# MCU.net
KiCad netlist of a schematic drawn in Altium Designer
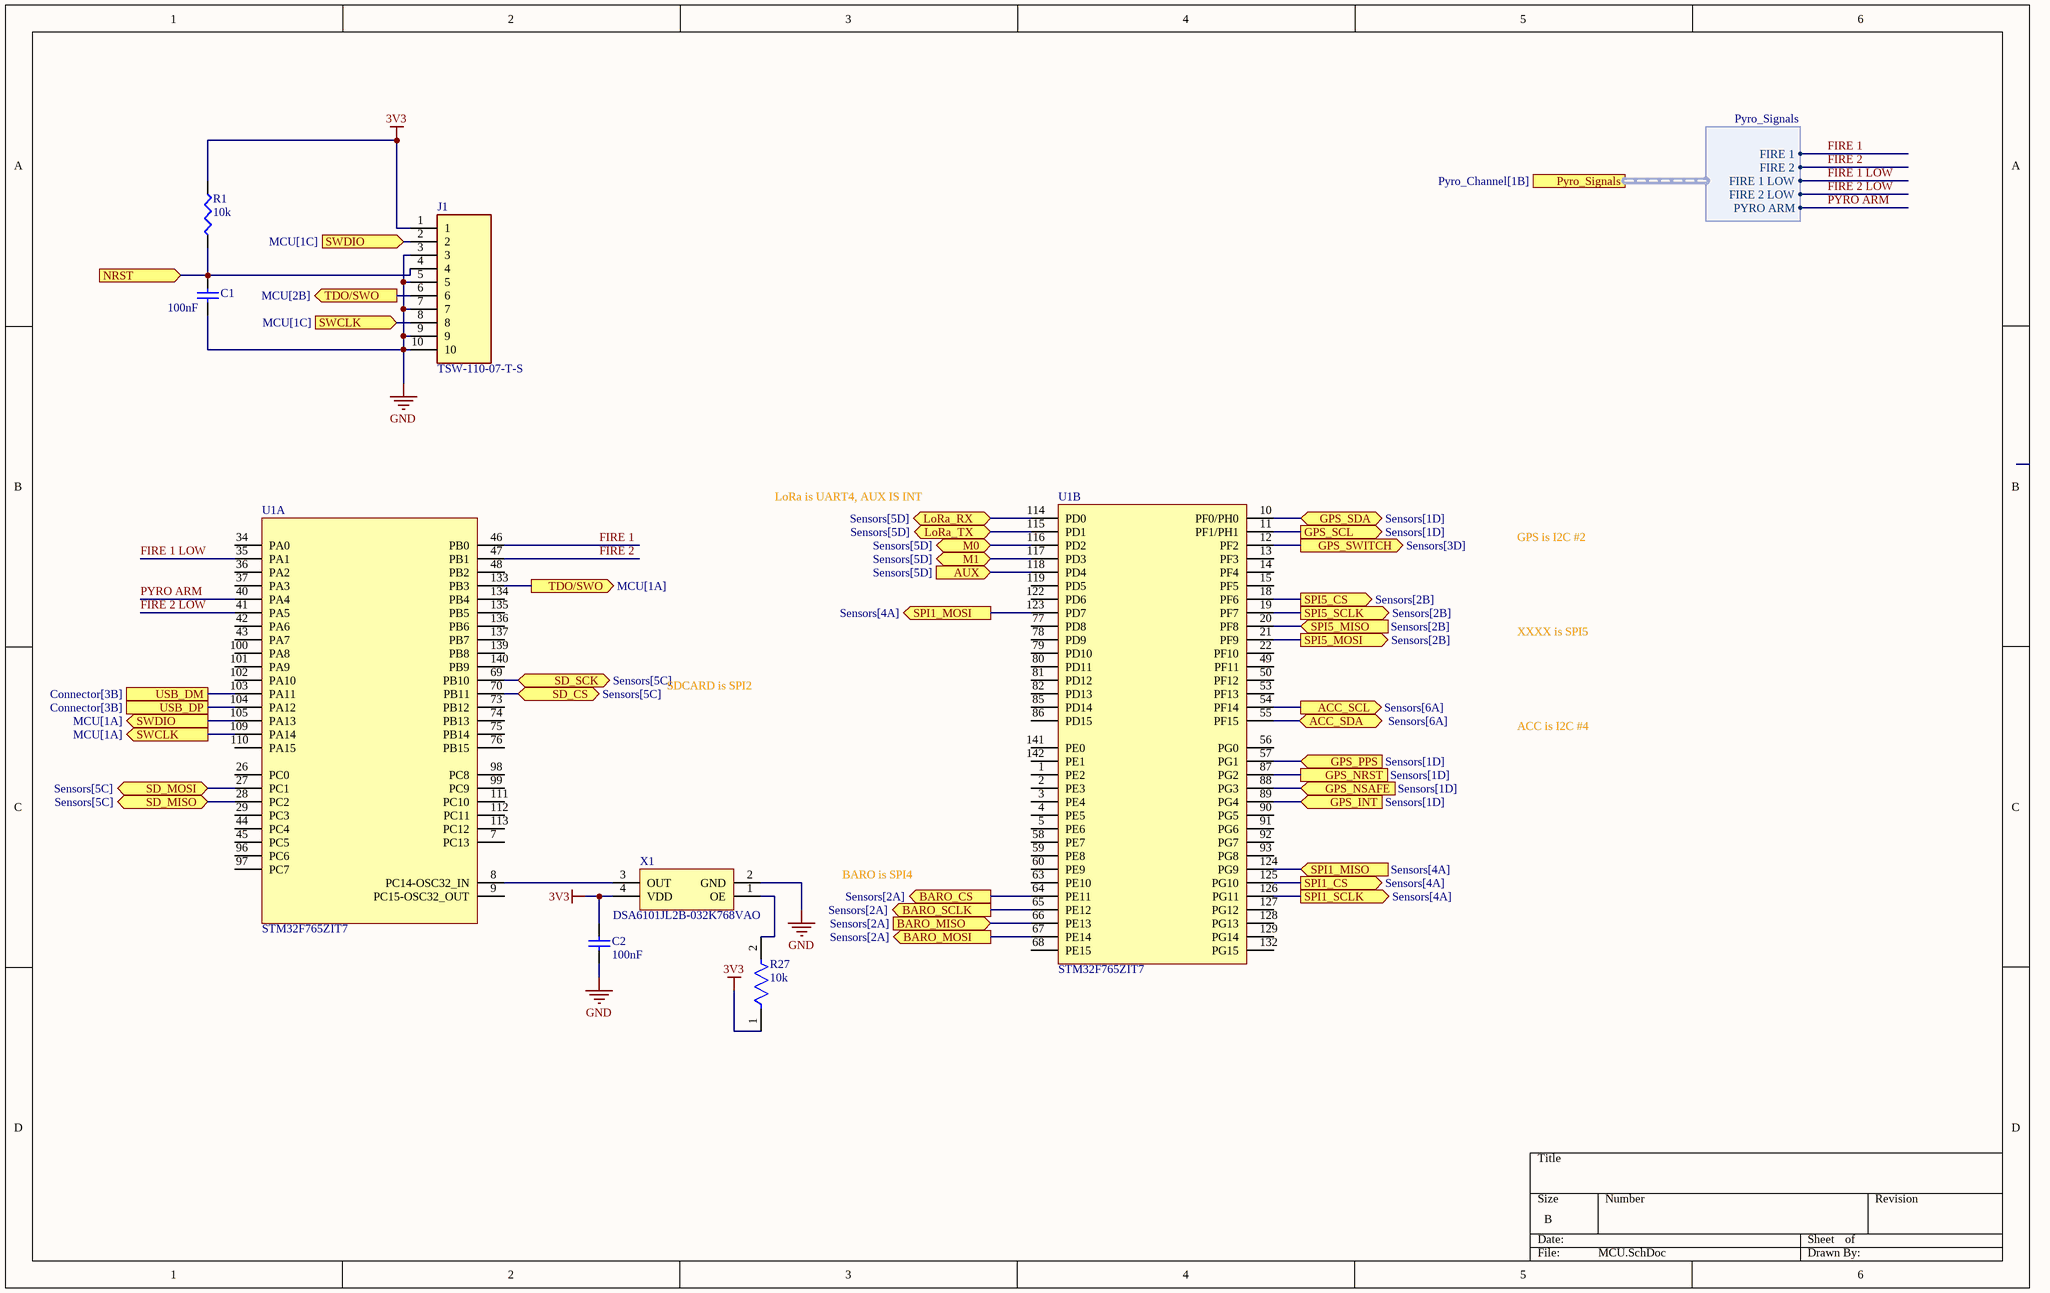
[diagram p0: MCU.SchDoc]

(export (version "E")
  (design (tool "Eeschema 10.0.6"))
  (components
    (comp (ref "C1")
      (value "100nF")
      (footprint "0402_C")
      (fields
        (field (name "MANUFACTURER") "Samsung Electro-Mechanics")
        (field (name "MANUFACTURER PART NUMBER") "CL05B104KO5NNNC")
        (field (name "TOLERANCE") "10%")
      )
      (libsource (lib "Flight_Computer1") (part "C_100nF_0402"))
    )
    (comp (ref "C2")
      (value "100nF")
      (footprint "0402_C")
      (fields
        (field (name "MANUFACTURER") "Samsung Electro-Mechanics")
        (field (name "MANUFACTURER PART NUMBER") "CL05B104KO5NNNC")
        (field (name "TOLERANCE") "10%")
      )
      (libsource (lib "Flight_Computer1") (part "C_100nF_0402"))
    )
    (comp (ref "J1")
      (value "TSW-110-07-T-S")
      (footprint "TSW-110-XX-YY-S")
      (description "CONN HEADER VERT 10POS 2.54MM")
      (fields (field (name "MOUSER PART NUMBER") "200-TSW11007TS") (field (name "MANUFACTURER") "Samtec"))
      (libsource (lib "Flight_Computer1") (part "TSW-110-07-T-S"))
    )
    (comp (ref "R1")
      (value "10k")
      (footprint "0402_R")
      (description "RES SMD 10K OHM 0.1% 1/16W 0402")
      (fields (field (name "LCSC PART #") "C191915") (field (name "MANUFACTURER") "Yageo Group"))
      (libsource (lib "Flight_Computer1") (part "R_10k_0402"))
    )
    (comp (ref "R27")
      (value "10k")
      (footprint "FP-AC0805-0_6-MFG")
      (description "RES SMD 0 OHM JUMPER 1/8W 0805")
      (fields (field (name "TOLERANCE") "5%"))
      (libsource (lib "Altium Content Vault") (part "1029c3af85768c4190bb7ad29bc67b5"))
    )
    (comp (ref "U1")
      (value "STM32F765ZIT7")
      (footprint "QFP50P2200X2200X160-144N")
      (description "Integrated Circuit")
      (fields (field (name "MOUSER PART NUMBER") "511-STM32F765ZIT7"))
      (libsource (lib "Flight_Computer1") (part "STM32F765ZIT7"))
    )
    (comp (ref "X1")
      (value "DSA6101JL2B-032K768VAO")
      (footprint "VLGA4_AUA_MCH")
      (description "Description")
      (fields (field (name "COPYRIGHT") "Copyright (C) 2025 Ultra Librarian. All rights reserved."))
      (libsource (lib "Americas - Purdue University - Purdue Space Program Hybrids") (part "DSA6101JL2B-032K768VAO"))
    )
  )
  (nets
    (net (code "2") (name "/ACC_SCL") (class "Default")
      (node (ref "U1") (pin "54") (pinfunction "PF14_54") (pintype "passive"))
    )
    (net (code "3") (name "/ACC_SDA") (class "Default")
      (node (ref "U1") (pin "55") (pinfunction "PF15_55") (pintype "passive"))
    )
    (net (code "4") (name "/AUX") (class "Default")
      (node (ref "U1") (pin "118") (pinfunction "PD4_118") (pintype "passive"))
    )
    (net (code "5") (name "/BARO_CS") (class "Default")
      (node (ref "U1") (pin "64") (pinfunction "PE11_64") (pintype "passive"))
    )
    (net (code "6") (name "/BARO_MISO") (class "Default")
      (node (ref "U1") (pin "66") (pinfunction "PE13_66") (pintype "passive"))
    )
    (net (code "7") (name "/BARO_MOSI") (class "Default")
      (node (ref "U1") (pin "67") (pinfunction "PE14_67") (pintype "passive"))
    )
    (net (code "8") (name "/BARO_SCLK") (class "Default")
      (node (ref "U1") (pin "65") (pinfunction "PE12_65") (pintype "passive"))
    )
    (net (code "9") (name "/FIRE 1") (class "Default")
      (node (ref "U1") (pin "46") (pinfunction "PB0_46") (pintype "passive"))
    )
    (net (code "10") (name "/FIRE 1 LOW") (class "Default")
      (node (ref "U1") (pin "35") (pinfunction "PA1_35") (pintype "passive"))
    )
    (net (code "11") (name "/FIRE 2") (class "Default")
      (node (ref "U1") (pin "47") (pinfunction "PB1_47") (pintype "passive"))
    )
    (net (code "12") (name "/FIRE 2 LOW") (class "Default")
      (node (ref "U1") (pin "41") (pinfunction "PA5_41") (pintype "passive"))
    )
    (net (code "13") (name "/GPS_INT") (class "Default")
      (node (ref "U1") (pin "89") (pinfunction "PG4_89") (pintype "passive"))
    )
    (net (code "14") (name "/GPS_NRST") (class "Default")
      (node (ref "U1") (pin "87") (pinfunction "PG2_87") (pintype "passive"))
    )
    (net (code "15") (name "/GPS_NSAFE") (class "Default")
      (node (ref "U1") (pin "88") (pinfunction "PG3_88") (pintype "passive"))
    )
    (net (code "16") (name "/GPS_PPS") (class "Default")
      (node (ref "U1") (pin "57") (pinfunction "PG1_57") (pintype "passive"))
    )
    (net (code "17") (name "/GPS_SCL") (class "Default")
      (node (ref "U1") (pin "11") (pinfunction "PF1/PH1_11") (pintype "passive"))
    )
    (net (code "18") (name "/GPS_SDA") (class "Default")
      (node (ref "U1") (pin "10") (pinfunction "PF0/PH0_10") (pintype "passive"))
    )
    (net (code "19") (name "/GPS_SWITCH") (class "Default")
      (node (ref "U1") (pin "12") (pinfunction "PF2_12") (pintype "passive"))
    )
    (net (code "20") (name "/LoRa_RX") (class "Default")
      (node (ref "U1") (pin "114") (pinfunction "PD0_114") (pintype "passive"))
    )
    (net (code "21") (name "/LoRa_TX") (class "Default")
      (node (ref "U1") (pin "115") (pinfunction "PD1_115") (pintype "passive"))
    )
    (net (code "22") (name "/M0") (class "Default")
      (node (ref "U1") (pin "116") (pinfunction "PD2_116") (pintype "passive"))
    )
    (net (code "23") (name "/M1") (class "Default")
      (node (ref "U1") (pin "117") (pinfunction "PD3_117") (pintype "passive"))
    )
    (net (code "24") (name "/NRST") (class "Default")
      (node (ref "C1") (pin "2") (pinfunction "2_2") (pintype "passive"))
      (node (ref "J1") (pin "4") (pinfunction "4_4") (pintype "passive"))
      (node (ref "R1") (pin "1") (pinfunction "1_1") (pintype "passive"))
    )
    (net (code "25") (name "/PYRO ARM") (class "Default")
      (node (ref "U1") (pin "40") (pinfunction "PA4_40") (pintype "passive"))
    )
    (net (code "26") (name "/SD_CS") (class "Default")
      (node (ref "U1") (pin "70") (pinfunction "PB11_70") (pintype "passive"))
    )
    (net (code "27") (name "/SD_MISO") (class "Default")
      (node (ref "U1") (pin "28") (pinfunction "PC2_28") (pintype "passive"))
    )
    (net (code "28") (name "/SD_MOSI") (class "Default")
      (node (ref "U1") (pin "27") (pinfunction "PC1_27") (pintype "passive"))
    )
    (net (code "29") (name "/SD_SCK") (class "Default")
      (node (ref "U1") (pin "69") (pinfunction "PB10_69") (pintype "passive"))
    )
    (net (code "30") (name "/SPI1_CS") (class "Default")
      (node (ref "U1") (pin "125") (pinfunction "PG10_125") (pintype "passive"))
    )
    (net (code "31") (name "/SPI1_MISO") (class "Default")
      (node (ref "U1") (pin "124") (pinfunction "PG9_124") (pintype "passive"))
    )
    (net (code "32") (name "/SPI1_MOSI") (class "Default")
      (node (ref "U1") (pin "123") (pinfunction "PD7_123") (pintype "passive"))
    )
    (net (code "33") (name "/SPI1_SCLK") (class "Default")
      (node (ref "U1") (pin "126") (pinfunction "PG11_126") (pintype "passive"))
    )
    (net (code "34") (name "/SPI5_CS") (class "Default")
      (node (ref "U1") (pin "18") (pinfunction "PF6_18") (pintype "passive"))
    )
    (net (code "35") (name "/SPI5_MISO") (class "Default")
      (node (ref "U1") (pin "20") (pinfunction "PF8_20") (pintype "passive"))
    )
    (net (code "36") (name "/SPI5_MOSI") (class "Default")
      (node (ref "U1") (pin "21") (pinfunction "PF9_21") (pintype "passive"))
    )
    (net (code "37") (name "/SPI5_SCLK") (class "Default")
      (node (ref "U1") (pin "19") (pinfunction "PF7_19") (pintype "passive"))
    )
    (net (code "38") (name "/SWCLK") (class "Default")
      (node (ref "J1") (pin "8") (pinfunction "8_8") (pintype "passive"))
      (node (ref "U1") (pin "109") (pinfunction "PA14_109") (pintype "passive"))
    )
    (net (code "39") (name "/SWDIO") (class "Default")
      (node (ref "J1") (pin "2") (pinfunction "2_2") (pintype "passive"))
      (node (ref "U1") (pin "105") (pinfunction "PA13_105") (pintype "passive"))
    )
    (net (code "40") (name "/TDO{slash}SWO") (class "Default")
      (node (ref "J1") (pin "6") (pinfunction "6_6") (pintype "passive"))
      (node (ref "U1") (pin "133") (pinfunction "PB3_133") (pintype "passive"))
    )
    (net (code "41") (name "/USB_DM") (class "Default")
      (node (ref "U1") (pin "103") (pinfunction "PA11_103") (pintype "passive"))
    )
    (net (code "42") (name "/USB_DP") (class "Default")
      (node (ref "U1") (pin "104") (pinfunction "PA12_104") (pintype "passive"))
    )
    (net (code "44") (name "3V3") (class "Default")
      (node (ref "C2") (pin "1") (pinfunction "1_1") (pintype "passive"))
      (node (ref "J1") (pin "1") (pinfunction "1_1") (pintype "passive"))
      (node (ref "R1") (pin "2") (pinfunction "2_2") (pintype "passive"))
      (node (ref "R27") (pin "1") (pinfunction "1_1") (pintype "passive"))
      (node (ref "X1") (pin "4") (pinfunction "VDD_4") (pintype "passive"))
    )
    (net (code "45") (name "GND") (class "Default")
      (node (ref "C1") (pin "1") (pinfunction "1_1") (pintype "passive"))
      (node (ref "C2") (pin "2") (pinfunction "2_2") (pintype "passive"))
      (node (ref "J1") (pin "10") (pinfunction "10_10") (pintype "passive"))
      (node (ref "J1") (pin "3") (pinfunction "3_3") (pintype "passive"))
      (node (ref "J1") (pin "5") (pinfunction "5_5") (pintype "passive"))
      (node (ref "J1") (pin "7") (pinfunction "7_7") (pintype "passive"))
      (node (ref "J1") (pin "9") (pinfunction "9_9") (pintype "passive"))
      (node (ref "X1") (pin "2") (pinfunction "GND_2") (pintype "passive"))
    )
    (net (code "46") (name "Net-(U1A-PC14-OSC32_IN)") (class "Default")
      (node (ref "U1") (pin "8") (pinfunction "PC14-OSC32_IN_8") (pintype "passive"))
      (node (ref "X1") (pin "3") (pinfunction "OUT_3") (pintype "passive"))
    )
    (net (code "47") (name "Net-(X1-OE)") (class "Default")
      (node (ref "R27") (pin "2") (pinfunction "2_2") (pintype "passive"))
      (node (ref "X1") (pin "1") (pinfunction "OE_1") (pintype "passive"))
    )
    (net (code "48") (name "unconnected-(U1A-PA0-Pad34)") (class "Default")
      (node (ref "U1") (pin "34") (pinfunction "PA0_34") (pintype "passive"))
    )
    (net (code "49") (name "unconnected-(U1A-PA2-Pad36)") (class "Default")
      (node (ref "U1") (pin "36") (pinfunction "PA2_36") (pintype "passive"))
    )
    (net (code "50") (name "unconnected-(U1A-PA3-Pad37)") (class "Default")
      (node (ref "U1") (pin "37") (pinfunction "PA3_37") (pintype "passive"))
    )
    (net (code "51") (name "unconnected-(U1A-PA6-Pad42)") (class "Default")
      (node (ref "U1") (pin "42") (pinfunction "PA6_42") (pintype "passive"))
    )
    (net (code "52") (name "unconnected-(U1A-PA7-Pad43)") (class "Default")
      (node (ref "U1") (pin "43") (pinfunction "PA7_43") (pintype "passive"))
    )
    (net (code "53") (name "unconnected-(U1A-PA8-Pad100)") (class "Default")
      (node (ref "U1") (pin "100") (pinfunction "PA8_100") (pintype "passive"))
    )
    (net (code "54") (name "unconnected-(U1A-PA9-Pad101)") (class "Default")
      (node (ref "U1") (pin "101") (pinfunction "PA9_101") (pintype "passive"))
    )
    (net (code "55") (name "unconnected-(U1A-PA10-Pad102)") (class "Default")
      (node (ref "U1") (pin "102") (pinfunction "PA10_102") (pintype "passive"))
    )
    (net (code "56") (name "unconnected-(U1A-PA15-Pad110)") (class "Default")
      (node (ref "U1") (pin "110") (pinfunction "PA15_110") (pintype "passive"))
    )
    (net (code "57") (name "unconnected-(U1A-PB2-Pad48)") (class "Default")
      (node (ref "U1") (pin "48") (pinfunction "PB2_48") (pintype "passive"))
    )
    (net (code "58") (name "unconnected-(U1A-PB4-Pad134)") (class "Default")
      (node (ref "U1") (pin "134") (pinfunction "PB4_134") (pintype "passive"))
    )
    (net (code "59") (name "unconnected-(U1A-PB5-Pad135)") (class "Default")
      (node (ref "U1") (pin "135") (pinfunction "PB5_135") (pintype "passive"))
    )
    (net (code "60") (name "unconnected-(U1A-PB6-Pad136)") (class "Default")
      (node (ref "U1") (pin "136") (pinfunction "PB6_136") (pintype "passive"))
    )
    (net (code "61") (name "unconnected-(U1A-PB7-Pad137)") (class "Default")
      (node (ref "U1") (pin "137") (pinfunction "PB7_137") (pintype "passive"))
    )
    (net (code "62") (name "unconnected-(U1A-PB8-Pad139)") (class "Default")
      (node (ref "U1") (pin "139") (pinfunction "PB8_139") (pintype "passive"))
    )
    (net (code "63") (name "unconnected-(U1A-PB9-Pad140)") (class "Default")
      (node (ref "U1") (pin "140") (pinfunction "PB9_140") (pintype "passive"))
    )
    (net (code "64") (name "unconnected-(U1A-PB12-Pad73)") (class "Default")
      (node (ref "U1") (pin "73") (pinfunction "PB12_73") (pintype "passive"))
    )
    (net (code "65") (name "unconnected-(U1A-PB13-Pad74)") (class "Default")
      (node (ref "U1") (pin "74") (pinfunction "PB13_74") (pintype "passive"))
    )
    (net (code "66") (name "unconnected-(U1A-PB14-Pad75)") (class "Default")
      (node (ref "U1") (pin "75") (pinfunction "PB14_75") (pintype "passive"))
    )
    (net (code "67") (name "unconnected-(U1A-PB15-Pad76)") (class "Default")
      (node (ref "U1") (pin "76") (pinfunction "PB15_76") (pintype "passive"))
    )
    (net (code "68") (name "unconnected-(U1A-PC0-Pad26)") (class "Default")
      (node (ref "U1") (pin "26") (pinfunction "PC0_26") (pintype "passive"))
    )
    (net (code "69") (name "unconnected-(U1A-PC3-Pad29)") (class "Default")
      (node (ref "U1") (pin "29") (pinfunction "PC3_29") (pintype "passive"))
    )
    (net (code "70") (name "unconnected-(U1A-PC4-Pad44)") (class "Default")
      (node (ref "U1") (pin "44") (pinfunction "PC4_44") (pintype "passive"))
    )
    (net (code "71") (name "unconnected-(U1A-PC5-Pad45)") (class "Default")
      (node (ref "U1") (pin "45") (pinfunction "PC5_45") (pintype "passive"))
    )
    (net (code "72") (name "unconnected-(U1A-PC6-Pad96)") (class "Default")
      (node (ref "U1") (pin "96") (pinfunction "PC6_96") (pintype "passive"))
    )
    (net (code "73") (name "unconnected-(U1A-PC7-Pad97)") (class "Default")
      (node (ref "U1") (pin "97") (pinfunction "PC7_97") (pintype "passive"))
    )
    (net (code "74") (name "unconnected-(U1A-PC8-Pad98)") (class "Default")
      (node (ref "U1") (pin "98") (pinfunction "PC8_98") (pintype "passive"))
    )
    (net (code "75") (name "unconnected-(U1A-PC9-Pad99)") (class "Default")
      (node (ref "U1") (pin "99") (pinfunction "PC9_99") (pintype "passive"))
    )
    (net (code "76") (name "unconnected-(U1A-PC10-Pad111)") (class "Default")
      (node (ref "U1") (pin "111") (pinfunction "PC10_111") (pintype "passive"))
    )
    (net (code "77") (name "unconnected-(U1A-PC11-Pad112)") (class "Default")
      (node (ref "U1") (pin "112") (pinfunction "PC11_112") (pintype "passive"))
    )
    (net (code "78") (name "unconnected-(U1A-PC12-Pad113)") (class "Default")
      (node (ref "U1") (pin "113") (pinfunction "PC12_113") (pintype "passive"))
    )
    (net (code "79") (name "unconnected-(U1A-PC13-Pad7)") (class "Default")
      (node (ref "U1") (pin "7") (pinfunction "PC13_7") (pintype "passive"))
    )
    (net (code "80") (name "unconnected-(U1A-PC15-OSC32_OUT-Pad9)") (class "Default")
      (node (ref "U1") (pin "9") (pinfunction "PC15-OSC32_OUT_9") (pintype "passive"))
    )
    (net (code "81") (name "unconnected-(U1B-PD5-Pad119)") (class "Default")
      (node (ref "U1") (pin "119") (pinfunction "PD5_119") (pintype "passive"))
    )
    (net (code "82") (name "unconnected-(U1B-PD6-Pad122)") (class "Default")
      (node (ref "U1") (pin "122") (pinfunction "PD6_122") (pintype "passive"))
    )
    (net (code "83") (name "unconnected-(U1B-PD8-Pad77)") (class "Default")
      (node (ref "U1") (pin "77") (pinfunction "PD8_77") (pintype "passive"))
    )
    (net (code "84") (name "unconnected-(U1B-PD9-Pad78)") (class "Default")
      (node (ref "U1") (pin "78") (pinfunction "PD9_78") (pintype "passive"))
    )
    (net (code "85") (name "unconnected-(U1B-PD10-Pad79)") (class "Default")
      (node (ref "U1") (pin "79") (pinfunction "PD10_79") (pintype "passive"))
    )
    (net (code "86") (name "unconnected-(U1B-PD11-Pad80)") (class "Default")
      (node (ref "U1") (pin "80") (pinfunction "PD11_80") (pintype "passive"))
    )
    (net (code "87") (name "unconnected-(U1B-PD12-Pad81)") (class "Default")
      (node (ref "U1") (pin "81") (pinfunction "PD12_81") (pintype "passive"))
    )
    (net (code "88") (name "unconnected-(U1B-PD13-Pad82)") (class "Default")
      (node (ref "U1") (pin "82") (pinfunction "PD13_82") (pintype "passive"))
    )
    (net (code "89") (name "unconnected-(U1B-PD14-Pad85)") (class "Default")
      (node (ref "U1") (pin "85") (pinfunction "PD14_85") (pintype "passive"))
    )
    (net (code "90") (name "unconnected-(U1B-PD15-Pad86)") (class "Default")
      (node (ref "U1") (pin "86") (pinfunction "PD15_86") (pintype "passive"))
    )
    (net (code "91") (name "unconnected-(U1B-PE0-Pad141)") (class "Default")
      (node (ref "U1") (pin "141") (pinfunction "PE0_141") (pintype "passive"))
    )
    (net (code "92") (name "unconnected-(U1B-PE1-Pad142)") (class "Default")
      (node (ref "U1") (pin "142") (pinfunction "PE1_142") (pintype "passive"))
    )
    (net (code "93") (name "unconnected-(U1B-PE2-Pad1)") (class "Default")
      (node (ref "U1") (pin "1") (pinfunction "PE2_1") (pintype "passive"))
    )
    (net (code "94") (name "unconnected-(U1B-PE3-Pad2)") (class "Default")
      (node (ref "U1") (pin "2") (pinfunction "PE3_2") (pintype "passive"))
    )
    (net (code "95") (name "unconnected-(U1B-PE4-Pad3)") (class "Default")
      (node (ref "U1") (pin "3") (pinfunction "PE4_3") (pintype "passive"))
    )
    (net (code "96") (name "unconnected-(U1B-PE5-Pad4)") (class "Default")
      (node (ref "U1") (pin "4") (pinfunction "PE5_4") (pintype "passive"))
    )
    (net (code "97") (name "unconnected-(U1B-PE6-Pad5)") (class "Default")
      (node (ref "U1") (pin "5") (pinfunction "PE6_5") (pintype "passive"))
    )
    (net (code "98") (name "unconnected-(U1B-PE7-Pad58)") (class "Default")
      (node (ref "U1") (pin "58") (pinfunction "PE7_58") (pintype "passive"))
    )
    (net (code "99") (name "unconnected-(U1B-PE8-Pad59)") (class "Default")
      (node (ref "U1") (pin "59") (pinfunction "PE8_59") (pintype "passive"))
    )
    (net (code "100") (name "unconnected-(U1B-PE9-Pad60)") (class "Default")
      (node (ref "U1") (pin "60") (pinfunction "PE9_60") (pintype "passive"))
    )
    (net (code "101") (name "unconnected-(U1B-PE10-Pad63)") (class "Default")
      (node (ref "U1") (pin "63") (pinfunction "PE10_63") (pintype "passive"))
    )
    (net (code "102") (name "unconnected-(U1B-PE15-Pad68)") (class "Default")
      (node (ref "U1") (pin "68") (pinfunction "PE15_68") (pintype "passive"))
    )
    (net (code "103") (name "unconnected-(U1B-PF3-Pad13)") (class "Default")
      (node (ref "U1") (pin "13") (pinfunction "PF3_13") (pintype "passive"))
    )
    (net (code "104") (name "unconnected-(U1B-PF4-Pad14)") (class "Default")
      (node (ref "U1") (pin "14") (pinfunction "PF4_14") (pintype "passive"))
    )
    (net (code "105") (name "unconnected-(U1B-PF5-Pad15)") (class "Default")
      (node (ref "U1") (pin "15") (pinfunction "PF5_15") (pintype "passive"))
    )
    (net (code "106") (name "unconnected-(U1B-PF10-Pad22)") (class "Default")
      (node (ref "U1") (pin "22") (pinfunction "PF10_22") (pintype "passive"))
    )
    (net (code "107") (name "unconnected-(U1B-PF11-Pad49)") (class "Default")
      (node (ref "U1") (pin "49") (pinfunction "PF11_49") (pintype "passive"))
    )
    (net (code "108") (name "unconnected-(U1B-PF12-Pad50)") (class "Default")
      (node (ref "U1") (pin "50") (pinfunction "PF12_50") (pintype "passive"))
    )
    (net (code "109") (name "unconnected-(U1B-PF13-Pad53)") (class "Default")
      (node (ref "U1") (pin "53") (pinfunction "PF13_53") (pintype "passive"))
    )
    (net (code "110") (name "unconnected-(U1B-PG0-Pad56)") (class "Default")
      (node (ref "U1") (pin "56") (pinfunction "PG0_56") (pintype "passive"))
    )
    (net (code "111") (name "unconnected-(U1B-PG5-Pad90)") (class "Default")
      (node (ref "U1") (pin "90") (pinfunction "PG5_90") (pintype "passive"))
    )
    (net (code "112") (name "unconnected-(U1B-PG6-Pad91)") (class "Default")
      (node (ref "U1") (pin "91") (pinfunction "PG6_91") (pintype "passive"))
    )
    (net (code "113") (name "unconnected-(U1B-PG7-Pad92)") (class "Default")
      (node (ref "U1") (pin "92") (pinfunction "PG7_92") (pintype "passive"))
    )
    (net (code "114") (name "unconnected-(U1B-PG8-Pad93)") (class "Default")
      (node (ref "U1") (pin "93") (pinfunction "PG8_93") (pintype "passive"))
    )
    (net (code "115") (name "unconnected-(U1B-PG12-Pad127)") (class "Default")
      (node (ref "U1") (pin "127") (pinfunction "PG12_127") (pintype "passive"))
    )
    (net (code "116") (name "unconnected-(U1B-PG13-Pad128)") (class "Default")
      (node (ref "U1") (pin "128") (pinfunction "PG13_128") (pintype "passive"))
    )
    (net (code "117") (name "unconnected-(U1B-PG14-Pad129)") (class "Default")
      (node (ref "U1") (pin "129") (pinfunction "PG14_129") (pintype "passive"))
    )
    (net (code "118") (name "unconnected-(U1B-PG15-Pad132)") (class "Default")
      (node (ref "U1") (pin "132") (pinfunction "PG15_132") (pintype "passive"))
    )
  )
)
